# EnvironmentMonitorV4.net
KiCad netlist of a schematic drawn in EAGLE
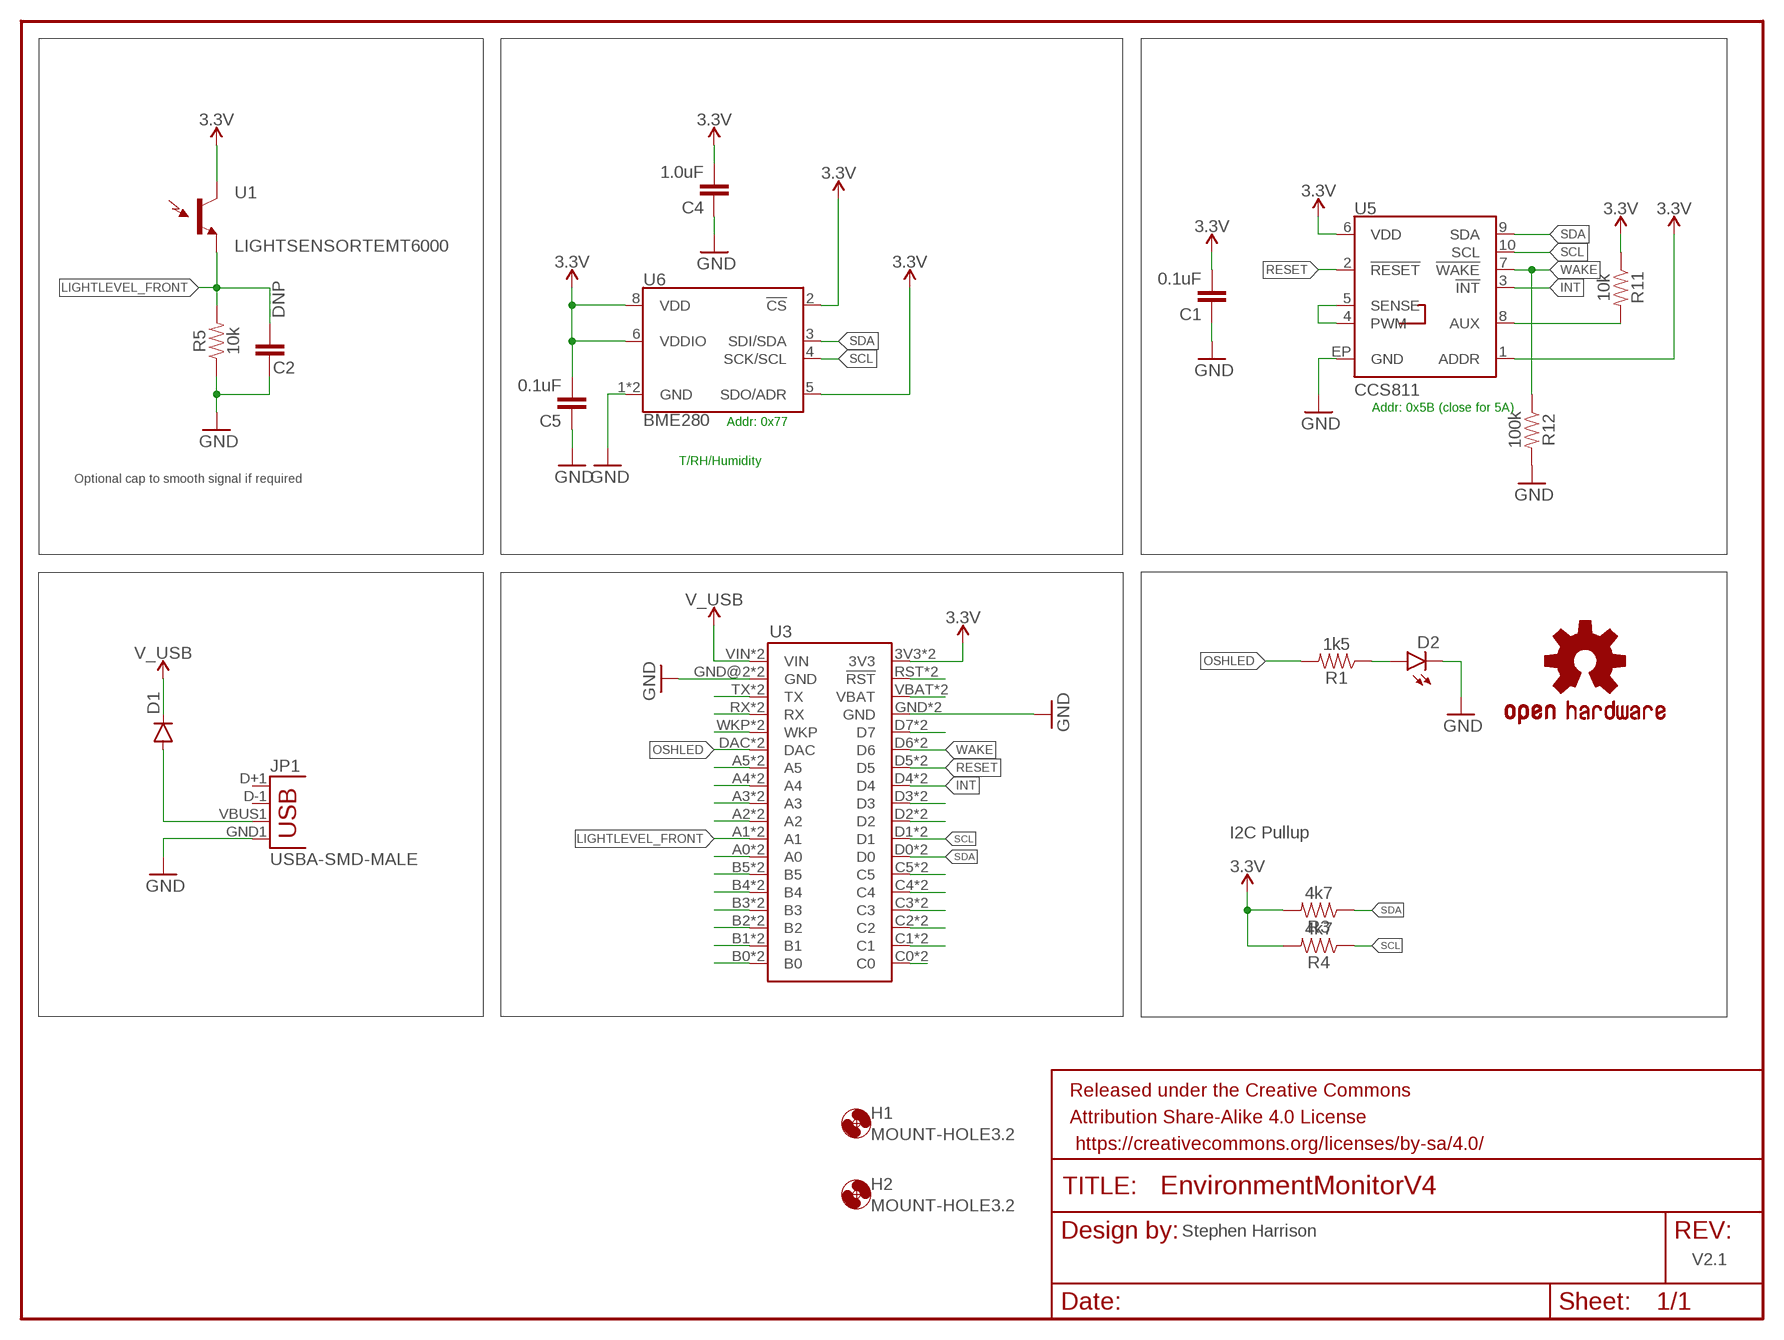
[diagram p0: schematic, sheet 1]

(export (version "E")
  (design (tool "Eeschema 10.0.6"))
  (components
    (comp (ref "C1")
      (value "0.1uF")
      (footprint "eagle-import:0805-CAP")
      (libsource (lib "eagle-import") (part "1.0UF-25V-+80/-20(0805){dblquote}"))
    )
    (comp (ref "C2")
      (value "DNP")
      (footprint "eagle-import:0805-CAP")
      (libsource (lib "eagle-import") (part "1.0UF-25V-+80/-20(0805){dblquote}"))
    )
    (comp (ref "C4")
      (value "1.0uF")
      (footprint "eagle-import:0805-CAP")
      (libsource (lib "eagle-import") (part "1.0UF-25V-+80/-20(0805){dblquote}"))
    )
    (comp (ref "C5")
      (value "0.1uF")
      (footprint "eagle-import:0805-CAP")
      (libsource (lib "eagle-import") (part "1.0UF-25V-+80/-20(0805){dblquote}"))
    )
    (comp (ref "D1")
      (value "DIODESMA")
      (footprint "eagle-import:SMA-DIODE")
      (libsource (lib "eagle-import") (part "DIODESMA"))
    )
    (comp (ref "D2")
      (value "LED1206-BOTTOM")
      (footprint "eagle-import:LED-1206-BOTTOM")
      (libsource (lib "eagle-import") (part "LED1206-BOTTOM"))
    )
    (comp (ref "FRAME1")
      (value "FRAME-LETTER")
      (footprint "eagle-import:CREATIVE_COMMONS")
      (libsource (lib "eagle-import") (part "FRAME-LETTER"))
    )
    (comp (ref "H1")
      (value "MOUNT-HOLE3.2")
      (footprint "eagle-import:3,2")
      (libsource (lib "eagle-import") (part "MOUNT-HOLE3.2"))
    )
    (comp (ref "H2")
      (value "MOUNT-HOLE3.2")
      (footprint "eagle-import:3,2")
      (libsource (lib "eagle-import") (part "MOUNT-HOLE3.2"))
    )
    (comp (ref "JP1")
      (value "USBA-SMD-MALE")
      (footprint "eagle-import:USB-A-SMT-MALE")
      (libsource (lib "eagle-import") (part "USBA-SMD-MALE"))
    )
    (comp (ref "LOGO1")
      (value "OSHW-LOGOM")
      (footprint "eagle-import:OSHW-LOGO-M")
      (libsource (lib "eagle-import") (part "OSHW-LOGOM"))
    )
    (comp (ref "R1")
      (value "1k5")
      (footprint "eagle-import:0805")
      (libsource (lib "eagle-import") (part "RESISTOR0805"))
    )
    (comp (ref "R3")
      (value "4k7")
      (footprint "eagle-import:0805")
      (libsource (lib "eagle-import") (part "RESISTOR0805"))
    )
    (comp (ref "R4")
      (value "4k7")
      (footprint "eagle-import:0805")
      (libsource (lib "eagle-import") (part "RESISTOR0805"))
    )
    (comp (ref "R5")
      (value "10k")
      (footprint "eagle-import:0805")
      (libsource (lib "eagle-import") (part "RESISTOR0805"))
    )
    (comp (ref "R11")
      (value "10k")
      (footprint "eagle-import:0805")
      (libsource (lib "eagle-import") (part "RESISTOR0805"))
    )
    (comp (ref "R12")
      (value "100k")
      (footprint "eagle-import:0805")
      (libsource (lib "eagle-import") (part "RESISTOR0805"))
    )
    (comp (ref "U1")
      (value "LIGHTSENSORTEMT6000")
      (footprint "eagle-import:TEMT6000-SEN")
      (libsource (lib "eagle-import") (part "LIGHTSENSORTEMT6000"))
    )
    (comp (ref "U3")
      (value "ELECTRONDUALNAMED")
      (footprint "eagle-import:ELECTRON_SIMPLE_SILK_NAMES_DUAL")
      (libsource (lib "eagle-import") (part "ELECTRONDUALNAMED"))
    )
    (comp (ref "U5")
      (value "CCS811")
      (footprint "eagle-import:LGA10")
      (libsource (lib "eagle-import") (part "CCS811"))
    )
    (comp (ref "U6")
      (value "BME280")
      (footprint "eagle-import:LGA-8-2.5X2.5")
      (libsource (lib "eagle-import") (part "BME280"))
    )
  )
  (nets
    (net (code "1") (name "3.3V") (class "Default")
      (node (ref "C1") (pin "2") (pinfunction "2_2") (pintype "passive"))
      (node (ref "C4") (pin "2") (pinfunction "2_2") (pintype "passive"))
      (node (ref "C5") (pin "2") (pinfunction "2_2") (pintype "passive"))
      (node (ref "R11") (pin "1") (pinfunction "1_1") (pintype "passive"))
      (node (ref "R3") (pin "2") (pinfunction "2_2") (pintype "passive"))
      (node (ref "R4") (pin "2") (pinfunction "2_2") (pintype "passive"))
      (node (ref "U1") (pin "COLLECTOR") (pinfunction "C1_COLLECTOR") (pintype "passive"))
      (node (ref "U3") (pin "3V3") (pinfunction "3V3_3V3") (pintype "power_in"))
      (node (ref "U3") (pin "3V3_1") (pinfunction "3V3_3V3_1") (pintype "power_in"))
      (node (ref "U5") (pin "1") (pinfunction "ADDR_1") (pintype "bidirectional"))
      (node (ref "U5") (pin "6") (pinfunction "VDD_6") (pintype "bidirectional"))
      (node (ref "U6") (pin "2") (pinfunction "~{CS}_2") (pintype "bidirectional"))
      (node (ref "U6") (pin "5") (pinfunction "SDO/ADR_5") (pintype "bidirectional"))
      (node (ref "U6") (pin "6") (pinfunction "VDDIO_6") (pintype "bidirectional"))
      (node (ref "U6") (pin "8") (pinfunction "VDD_8") (pintype "bidirectional"))
    )
    (net (code "2") (name "GND") (class "Default")
      (node (ref "C1") (pin "1") (pinfunction "1_1") (pintype "passive"))
      (node (ref "C2") (pin "1") (pinfunction "1_1") (pintype "passive"))
      (node (ref "C4") (pin "1") (pinfunction "1_1") (pintype "passive"))
      (node (ref "C5") (pin "1") (pinfunction "1_1") (pintype "passive"))
      (node (ref "D2") (pin "C") (pinfunction "C_C") (pintype "passive"))
      (node (ref "JP1") (pin "GND1") (pinfunction "GND_GND1") (pintype "bidirectional"))
      (node (ref "R12") (pin "2") (pinfunction "2_2") (pintype "passive"))
      (node (ref "R5") (pin "1") (pinfunction "1_1") (pintype "passive"))
      (node (ref "U3") (pin "GND") (pinfunction "GND_GND") (pintype "power_in"))
      (node (ref "U3") (pin "GND@2") (pinfunction "GND_GND@2") (pintype "power_in"))
      (node (ref "U3") (pin "GND_1") (pinfunction "GND_GND_1") (pintype "power_in"))
      (node (ref "U3") (pin "GND_1B") (pinfunction "GND_GND_1B") (pintype "power_in"))
      (node (ref "U5") (pin "EP") (pinfunction "GND_EP") (pintype "bidirectional"))
      (node (ref "U6") (pin "1") (pinfunction "GND_1") (pintype "bidirectional"))
      (node (ref "U6") (pin "7") (pinfunction "GND_7") (pintype "bidirectional"))
    )
    (net (code "3") (name "INT") (class "Default")
      (node (ref "U3") (pin "D4") (pinfunction "D4_D4") (pintype "bidirectional"))
      (node (ref "U3") (pin "D4_1") (pinfunction "D4_D4_1") (pintype "bidirectional"))
      (node (ref "U5") (pin "3") (pinfunction "~{INT}_3") (pintype "bidirectional"))
    )
    (net (code "4") (name "LIGHTLEVEL_FRONT") (class "Default")
      (node (ref "C2") (pin "2") (pinfunction "2_2") (pintype "passive"))
      (node (ref "R5") (pin "2") (pinfunction "2_2") (pintype "passive"))
      (node (ref "U1") (pin "EMITTER") (pinfunction "E1_EMITTER") (pintype "passive"))
      (node (ref "U3") (pin "A1") (pinfunction "A1_A1") (pintype "bidirectional"))
      (node (ref "U3") (pin "A1_1") (pinfunction "A1_A1_1") (pintype "bidirectional"))
    )
    (net (code "5") (name "Net-(D2-PadA)") (class "Default")
      (node (ref "D2") (pin "A") (pinfunction "A_A") (pintype "passive"))
      (node (ref "R1") (pin "1") (pinfunction "1_1") (pintype "passive"))
    )
    (net (code "6") (name "Net-(JP1-VBUS)") (class "Default")
      (node (ref "D1") (pin "A") (pinfunction "A_A") (pintype "passive"))
      (node (ref "JP1") (pin "VBUS1") (pinfunction "VBUS_VBUS1") (pintype "bidirectional"))
    )
    (net (code "7") (name "Net-(U3-A0-PadA0_1)") (class "Default")
      (node (ref "U3") (pin "A0") (pinfunction "A0_A0") (pintype "bidirectional"))
      (node (ref "U3") (pin "A0_1") (pinfunction "A0_A0_1") (pintype "bidirectional"))
    )
    (net (code "8") (name "Net-(U3-A2-PadA2_1)") (class "Default")
      (node (ref "U3") (pin "A2") (pinfunction "A2_A2") (pintype "bidirectional"))
      (node (ref "U3") (pin "A2_1") (pinfunction "A2_A2_1") (pintype "bidirectional"))
    )
    (net (code "9") (name "Net-(U3-A3-PadA3_1)") (class "Default")
      (node (ref "U3") (pin "A3") (pinfunction "A3_A3") (pintype "bidirectional"))
      (node (ref "U3") (pin "A3_1") (pinfunction "A3_A3_1") (pintype "bidirectional"))
    )
    (net (code "10") (name "Net-(U3-A4-PadA4_1)") (class "Default")
      (node (ref "U3") (pin "A4") (pinfunction "A4_A4") (pintype "bidirectional"))
      (node (ref "U3") (pin "A4_1") (pinfunction "A4_A4_1") (pintype "bidirectional"))
    )
    (net (code "11") (name "Net-(U3-A5-PadA5_1)") (class "Default")
      (node (ref "U3") (pin "A5") (pinfunction "A5_A5") (pintype "bidirectional"))
      (node (ref "U3") (pin "A5_1") (pinfunction "A5_A5_1") (pintype "bidirectional"))
    )
    (net (code "12") (name "Net-(U3-B0-PadB0_1)") (class "Default")
      (node (ref "U3") (pin "B0") (pinfunction "B0_B0") (pintype "bidirectional"))
      (node (ref "U3") (pin "B0_1") (pinfunction "B0_B0_1") (pintype "bidirectional"))
    )
    (net (code "13") (name "Net-(U3-B1-PadB1_1)") (class "Default")
      (node (ref "U3") (pin "B1") (pinfunction "B1_B1") (pintype "bidirectional"))
      (node (ref "U3") (pin "B1_1") (pinfunction "B1_B1_1") (pintype "bidirectional"))
    )
    (net (code "14") (name "Net-(U3-B2-PadB2_1)") (class "Default")
      (node (ref "U3") (pin "B2") (pinfunction "B2_B2") (pintype "bidirectional"))
      (node (ref "U3") (pin "B2_1") (pinfunction "B2_B2_1") (pintype "bidirectional"))
    )
    (net (code "15") (name "Net-(U3-B3-PadB3_1)") (class "Default")
      (node (ref "U3") (pin "B3") (pinfunction "B3_B3") (pintype "bidirectional"))
      (node (ref "U3") (pin "B3_1") (pinfunction "B3_B3_1") (pintype "bidirectional"))
    )
    (net (code "16") (name "Net-(U3-B4-PadB4_1)") (class "Default")
      (node (ref "U3") (pin "B4") (pinfunction "B4_B4") (pintype "bidirectional"))
      (node (ref "U3") (pin "B4_1") (pinfunction "B4_B4_1") (pintype "bidirectional"))
    )
    (net (code "17") (name "Net-(U3-B5-PadB5_1)") (class "Default")
      (node (ref "U3") (pin "B5") (pinfunction "B5_B5") (pintype "bidirectional"))
      (node (ref "U3") (pin "B5_1") (pinfunction "B5_B5_1") (pintype "bidirectional"))
    )
    (net (code "18") (name "Net-(U3-C0-PadC0_1)") (class "Default")
      (node (ref "U3") (pin "C0") (pinfunction "C0_C0") (pintype "bidirectional"))
      (node (ref "U3") (pin "C0_1") (pinfunction "C0_C0_1") (pintype "bidirectional"))
    )
    (net (code "19") (name "Net-(U3-C1-PadC1_1)") (class "Default")
      (node (ref "U3") (pin "C1") (pinfunction "C1_C1") (pintype "bidirectional"))
      (node (ref "U3") (pin "C1_1") (pinfunction "C1_C1_1") (pintype "bidirectional"))
    )
    (net (code "20") (name "Net-(U3-C2-PadC2_1)") (class "Default")
      (node (ref "U3") (pin "C2") (pinfunction "C2_C2") (pintype "bidirectional"))
      (node (ref "U3") (pin "C2_1") (pinfunction "C2_C2_1") (pintype "bidirectional"))
    )
    (net (code "21") (name "Net-(U3-C3-PadC3_1)") (class "Default")
      (node (ref "U3") (pin "C3") (pinfunction "C3_C3") (pintype "bidirectional"))
      (node (ref "U3") (pin "C3_1") (pinfunction "C3_C3_1") (pintype "bidirectional"))
    )
    (net (code "22") (name "Net-(U3-C4-PadC4_1)") (class "Default")
      (node (ref "U3") (pin "C4") (pinfunction "C4_C4") (pintype "bidirectional"))
      (node (ref "U3") (pin "C4_1") (pinfunction "C4_C4_1") (pintype "bidirectional"))
    )
    (net (code "23") (name "Net-(U3-C5-PadC5_1)") (class "Default")
      (node (ref "U3") (pin "C5") (pinfunction "C5_C5") (pintype "bidirectional"))
      (node (ref "U3") (pin "C5_1") (pinfunction "C5_C5_1") (pintype "bidirectional"))
    )
    (net (code "24") (name "Net-(U3-D2-PadD2_1)") (class "Default")
      (node (ref "U3") (pin "D2") (pinfunction "D2_D2") (pintype "bidirectional"))
      (node (ref "U3") (pin "D2_1") (pinfunction "D2_D2_1") (pintype "bidirectional"))
    )
    (net (code "25") (name "Net-(U3-D3-PadD3_1)") (class "Default")
      (node (ref "U3") (pin "D3") (pinfunction "D3_D3") (pintype "bidirectional"))
      (node (ref "U3") (pin "D3_1") (pinfunction "D3_D3_1") (pintype "bidirectional"))
    )
    (net (code "26") (name "Net-(U3-D7-PadD7_1)") (class "Default")
      (node (ref "U3") (pin "D7") (pinfunction "D7_D7") (pintype "bidirectional"))
      (node (ref "U3") (pin "D7_1") (pinfunction "D7_D7_1") (pintype "bidirectional"))
    )
    (net (code "27") (name "Net-(U3-PadRX)") (class "Default")
      (node (ref "U3") (pin "RX") (pinfunction "RX_RX") (pintype "bidirectional"))
      (node (ref "U3") (pin "RX_1") (pinfunction "RX_RX_1") (pintype "bidirectional"))
    )
    (net (code "28") (name "Net-(U3-PadTX)") (class "Default")
      (node (ref "U3") (pin "TX") (pinfunction "TX_TX") (pintype "bidirectional"))
      (node (ref "U3") (pin "TX_1") (pinfunction "TX_TX_1") (pintype "bidirectional"))
    )
    (net (code "29") (name "Net-(U3-PadVBAT)") (class "Default")
      (node (ref "U3") (pin "VBAT") (pinfunction "VBAT_VBAT") (pintype "passive"))
      (node (ref "U3") (pin "VBATT_1") (pinfunction "VBAT_VBATT_1") (pintype "passive"))
    )
    (net (code "30") (name "Net-(U3-PadWKP)") (class "Default")
      (node (ref "U3") (pin "WKP") (pinfunction "WKP_WKP") (pintype "bidirectional"))
      (node (ref "U3") (pin "WKP_1") (pinfunction "WKP_WKP_1") (pintype "bidirectional"))
    )
    (net (code "31") (name "Net-(U3-~{RST}-PadRST)") (class "Default")
      (node (ref "U3") (pin "RST") (pinfunction "~{RST}_RST") (pintype "bidirectional"))
      (node (ref "U3") (pin "RST_1") (pinfunction "~{RST}_RST_1") (pintype "bidirectional"))
    )
    (net (code "32") (name "Net-(U5-AUX)") (class "Default")
      (node (ref "R11") (pin "2") (pinfunction "2_2") (pintype "passive"))
      (node (ref "U5") (pin "8") (pinfunction "AUX_8") (pintype "bidirectional"))
    )
    (net (code "33") (name "Net-(U5-PWM)") (class "Default")
      (node (ref "U5") (pin "4") (pinfunction "PWM_4") (pintype "bidirectional"))
      (node (ref "U5") (pin "5") (pinfunction "SENSE_5") (pintype "bidirectional"))
    )
    (net (code "34") (name "OSHLED") (class "Default")
      (node (ref "R1") (pin "2") (pinfunction "2_2") (pintype "passive"))
      (node (ref "U3") (pin "DAC") (pinfunction "DAC_DAC") (pintype "bidirectional"))
      (node (ref "U3") (pin "DAC_1") (pinfunction "DAC_DAC_1") (pintype "bidirectional"))
    )
    (net (code "35") (name "RESET") (class "Default")
      (node (ref "U3") (pin "D5") (pinfunction "D5_D5") (pintype "bidirectional"))
      (node (ref "U3") (pin "D5_1") (pinfunction "D5_D5_1") (pintype "bidirectional"))
      (node (ref "U5") (pin "2") (pinfunction "~{RESET}_2") (pintype "bidirectional"))
    )
    (net (code "36") (name "SCL") (class "Default")
      (node (ref "R4") (pin "1") (pinfunction "1_1") (pintype "passive"))
      (node (ref "U3") (pin "D1") (pinfunction "D1_D1") (pintype "bidirectional"))
      (node (ref "U3") (pin "D1_1") (pinfunction "D1_D1_1") (pintype "bidirectional"))
      (node (ref "U5") (pin "10") (pinfunction "SCL_10") (pintype "bidirectional"))
      (node (ref "U6") (pin "4") (pinfunction "SCK/SCL_4") (pintype "bidirectional"))
    )
    (net (code "37") (name "SDA") (class "Default")
      (node (ref "R3") (pin "1") (pinfunction "1_1") (pintype "passive"))
      (node (ref "U3") (pin "D0") (pinfunction "D0_D0") (pintype "bidirectional"))
      (node (ref "U3") (pin "D0_1") (pinfunction "D0_D0_1") (pintype "bidirectional"))
      (node (ref "U5") (pin "9") (pinfunction "SDA_9") (pintype "bidirectional"))
      (node (ref "U6") (pin "3") (pinfunction "SDI/SDA_3") (pintype "bidirectional"))
    )
    (net (code "38") (name "V_USB") (class "Default")
      (node (ref "D1") (pin "C") (pinfunction "C_C") (pintype "passive"))
      (node (ref "U3") (pin "VIN") (pinfunction "VIN_VIN") (pintype "power_in"))
      (node (ref "U3") (pin "VIN_1B") (pinfunction "VIN_VIN_1B") (pintype "power_in"))
    )
    (net (code "39") (name "WAKE") (class "Default")
      (node (ref "R12") (pin "1") (pinfunction "1_1") (pintype "passive"))
      (node (ref "U3") (pin "D6") (pinfunction "D6_D6") (pintype "bidirectional"))
      (node (ref "U3") (pin "D6_1") (pinfunction "D6_D6_1") (pintype "bidirectional"))
      (node (ref "U5") (pin "7") (pinfunction "~{WAKE}_7") (pintype "bidirectional"))
    )
    (net (code "40") (name "unconnected-(JP1-D+-PadD+1)") (class "Default")
      (node (ref "JP1") (pin "D+1") (pinfunction "D+_D+1") (pintype "bidirectional"))
    )
    (net (code "41") (name "unconnected-(JP1-D--PadD-1)") (class "Default")
      (node (ref "JP1") (pin "D-1") (pinfunction "D-_D-1") (pintype "bidirectional"))
    )
  )
)
